# SensorBoardR1.net
KiCad netlist of a schematic drawn in EAGLE
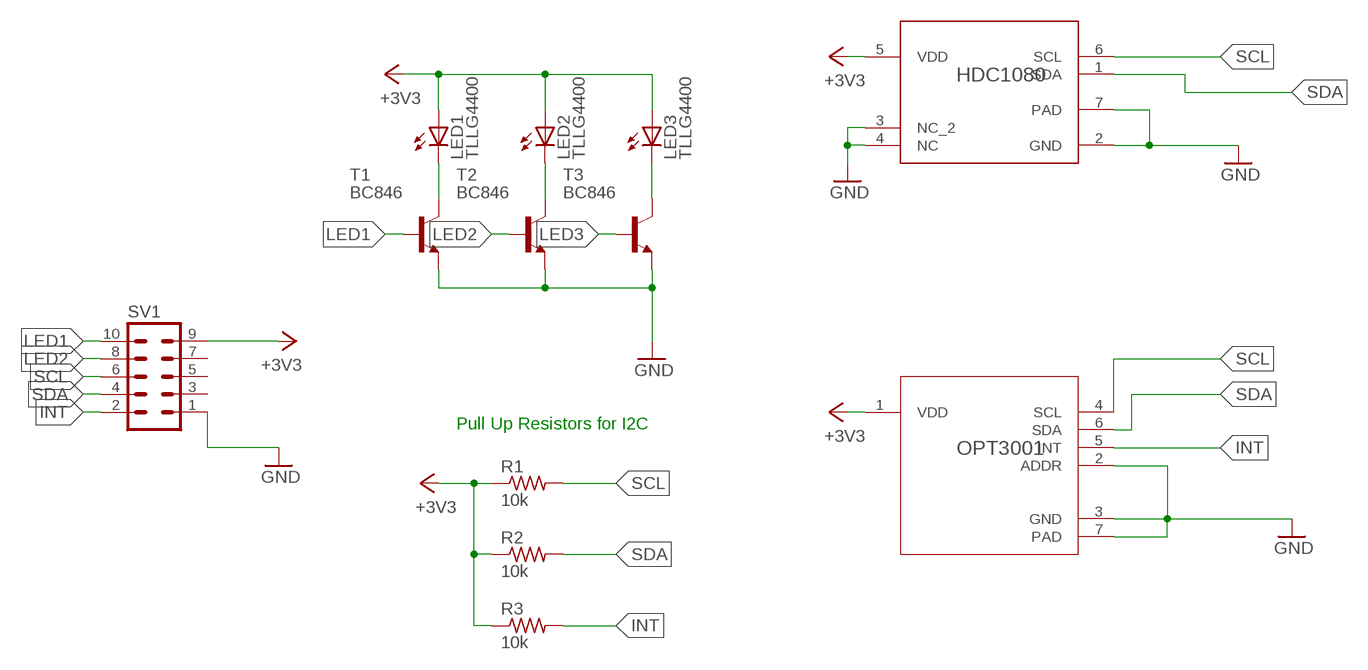
[diagram p0: schematic, sheet 1]

(export (version "E")
  (design (tool "Eeschema 10.0.6"))
  (components
    (comp (ref "HDC1080")
      (value "HDC1080DMBR")
      (footprint "eagle-import:DMB0006A")
      (fields
        (field (name "ALTERNATEPARTNUMBER") "HDC1080DMBT")
        (field (name "MANUFACTURER") "Texas Instruments")
      )
      (libsource (lib "eagle-import") (part "HDC1080DMBR"))
    )
    (comp (ref "LED1")
      (value "TLLG4400")
      (footprint "eagle-import:LED3MM")
      (fields (field (name "MF") "VISHAY SEMICONDUCTOR"))
      (libsource (lib "eagle-import") (part "TLLG4400"))
    )
    (comp (ref "LED2")
      (value "TLLG4400")
      (footprint "eagle-import:LED3MM")
      (fields (field (name "MF") "VISHAY SEMICONDUCTOR"))
      (libsource (lib "eagle-import") (part "TLLG4400"))
    )
    (comp (ref "LED3")
      (value "TLLG4400")
      (footprint "eagle-import:LED3MM")
      (fields (field (name "MF") "VISHAY SEMICONDUCTOR"))
      (libsource (lib "eagle-import") (part "TLLG4400"))
    )
    (comp (ref "OPT3001")
      (value "OPT3001DNPR")
      (footprint "eagle-import:DNP0006A")
      (fields (field (name "MANUFACTURER") "Texas Instruments") (field (name "PARTNUMBER") "OPT3001DNP"))
      (libsource (lib "eagle-import") (part "OPT3001DNPR"))
    )
    (comp (ref "R1")
      (value "10k")
      (footprint "eagle-import:R0805")
      (libsource (lib "eagle-import") (part "R-US_R0805"))
    )
    (comp (ref "R2")
      (value "10k")
      (footprint "eagle-import:R0805")
      (libsource (lib "eagle-import") (part "R-US_R0805"))
    )
    (comp (ref "R3")
      (value "10k")
      (footprint "eagle-import:R0805")
      (libsource (lib "eagle-import") (part "R-US_R0805"))
    )
    (comp (ref "SV1")
      (value "MA05-2")
      (footprint "eagle-import:MA05-2")
      (libsource (lib "eagle-import") (part "MA05-2"))
    )
    (comp (ref "T1")
      (value "BC846")
      (footprint "eagle-import:SOT23")
      (libsource (lib "eagle-import") (part "BC846"))
    )
    (comp (ref "T2")
      (value "BC846")
      (footprint "eagle-import:SOT23")
      (libsource (lib "eagle-import") (part "BC846"))
    )
    (comp (ref "T3")
      (value "BC846")
      (footprint "eagle-import:SOT23")
      (libsource (lib "eagle-import") (part "BC846"))
    )
  )
  (nets
    (net (code "1") (name "+3V3") (class "Default")
      (node (ref "HDC1080") (pin "5") (pinfunction "VDD_5") (pintype "power_in"))
      (node (ref "LED1") (pin "A") (pinfunction "A_A") (pintype "passive"))
      (node (ref "LED2") (pin "A") (pinfunction "A_A") (pintype "passive"))
      (node (ref "LED3") (pin "A") (pinfunction "A_A") (pintype "passive"))
      (node (ref "OPT3001") (pin "1") (pinfunction "VDD_1") (pintype "power_in"))
      (node (ref "R1") (pin "1") (pinfunction "1_1") (pintype "passive"))
      (node (ref "R2") (pin "1") (pinfunction "1_1") (pintype "passive"))
      (node (ref "R3") (pin "1") (pinfunction "1_1") (pintype "passive"))
      (node (ref "SV1") (pin "9") (pinfunction "9_9") (pintype "passive"))
    )
    (net (code "2") (name "GND") (class "Default")
      (node (ref "HDC1080") (pin "2") (pinfunction "GND_2") (pintype "power_in"))
      (node (ref "HDC1080") (pin "3") (pinfunction "NC_2_3") (pintype "passive"))
      (node (ref "HDC1080") (pin "4") (pinfunction "NC_4") (pintype "passive"))
      (node (ref "HDC1080") (pin "7") (pinfunction "PAD_7") (pintype "power_in"))
      (node (ref "OPT3001") (pin "2") (pinfunction "ADDR_2") (pintype "input"))
      (node (ref "OPT3001") (pin "3") (pinfunction "GND_3") (pintype "power_in"))
      (node (ref "OPT3001") (pin "7") (pinfunction "PAD_7") (pintype "passive"))
      (node (ref "SV1") (pin "1") (pinfunction "1_1") (pintype "passive"))
      (node (ref "T1") (pin "2") (pinfunction "E_2") (pintype "passive"))
      (node (ref "T2") (pin "2") (pinfunction "E_2") (pintype "passive"))
      (node (ref "T3") (pin "2") (pinfunction "E_2") (pintype "passive"))
    )
    (net (code "3") (name "INT") (class "Default")
      (node (ref "OPT3001") (pin "5") (pinfunction "INT_5") (pintype "output"))
      (node (ref "R3") (pin "2") (pinfunction "2_2") (pintype "passive"))
      (node (ref "SV1") (pin "2") (pinfunction "2_2") (pintype "passive"))
    )
    (net (code "4") (name "LED1") (class "Default")
      (node (ref "SV1") (pin "10") (pinfunction "10_10") (pintype "passive"))
      (node (ref "T1") (pin "1") (pinfunction "B_1") (pintype "passive"))
    )
    (net (code "5") (name "LED2") (class "Default")
      (node (ref "SV1") (pin "8") (pinfunction "8_8") (pintype "passive"))
      (node (ref "T2") (pin "1") (pinfunction "B_1") (pintype "passive"))
    )
    (net (code "6") (name "LED3") (class "Default")
      (node (ref "T3") (pin "1") (pinfunction "B_1") (pintype "passive"))
    )
    (net (code "7") (name "Net-(LED1-C)") (class "Default")
      (node (ref "LED1") (pin "K") (pinfunction "C_K") (pintype "passive"))
      (node (ref "T1") (pin "3") (pinfunction "C_3") (pintype "passive"))
    )
    (net (code "8") (name "Net-(LED2-C)") (class "Default")
      (node (ref "LED2") (pin "K") (pinfunction "C_K") (pintype "passive"))
      (node (ref "T2") (pin "3") (pinfunction "C_3") (pintype "passive"))
    )
    (net (code "9") (name "Net-(LED3-C)") (class "Default")
      (node (ref "LED3") (pin "K") (pinfunction "C_K") (pintype "passive"))
      (node (ref "T3") (pin "3") (pinfunction "C_3") (pintype "passive"))
    )
    (net (code "10") (name "SCL") (class "Default")
      (node (ref "HDC1080") (pin "6") (pinfunction "SCL_6") (pintype "open_collector"))
      (node (ref "OPT3001") (pin "4") (pinfunction "SCL_4") (pintype "input"))
      (node (ref "R1") (pin "2") (pinfunction "2_2") (pintype "passive"))
      (node (ref "SV1") (pin "6") (pinfunction "6_6") (pintype "passive"))
    )
    (net (code "11") (name "SDA") (class "Default")
      (node (ref "HDC1080") (pin "1") (pinfunction "SDA_1") (pintype "bidirectional"))
      (node (ref "OPT3001") (pin "6") (pinfunction "SDA_6") (pintype "input"))
      (node (ref "R2") (pin "2") (pinfunction "2_2") (pintype "passive"))
      (node (ref "SV1") (pin "4") (pinfunction "4_4") (pintype "passive"))
    )
    (net (code "12") (name "unconnected-(SV1-Pad3)") (class "Default")
      (node (ref "SV1") (pin "3") (pinfunction "3_3") (pintype "passive"))
    )
    (net (code "13") (name "unconnected-(SV1-Pad5)") (class "Default")
      (node (ref "SV1") (pin "5") (pinfunction "5_5") (pintype "passive"))
    )
    (net (code "14") (name "unconnected-(SV1-Pad7)") (class "Default")
      (node (ref "SV1") (pin "7") (pinfunction "7_7") (pintype "passive"))
    )
  )
)
